# CaRe_Schematic_SMD_6_29.net
KiCad netlist of a schematic drawn in Altium Designer
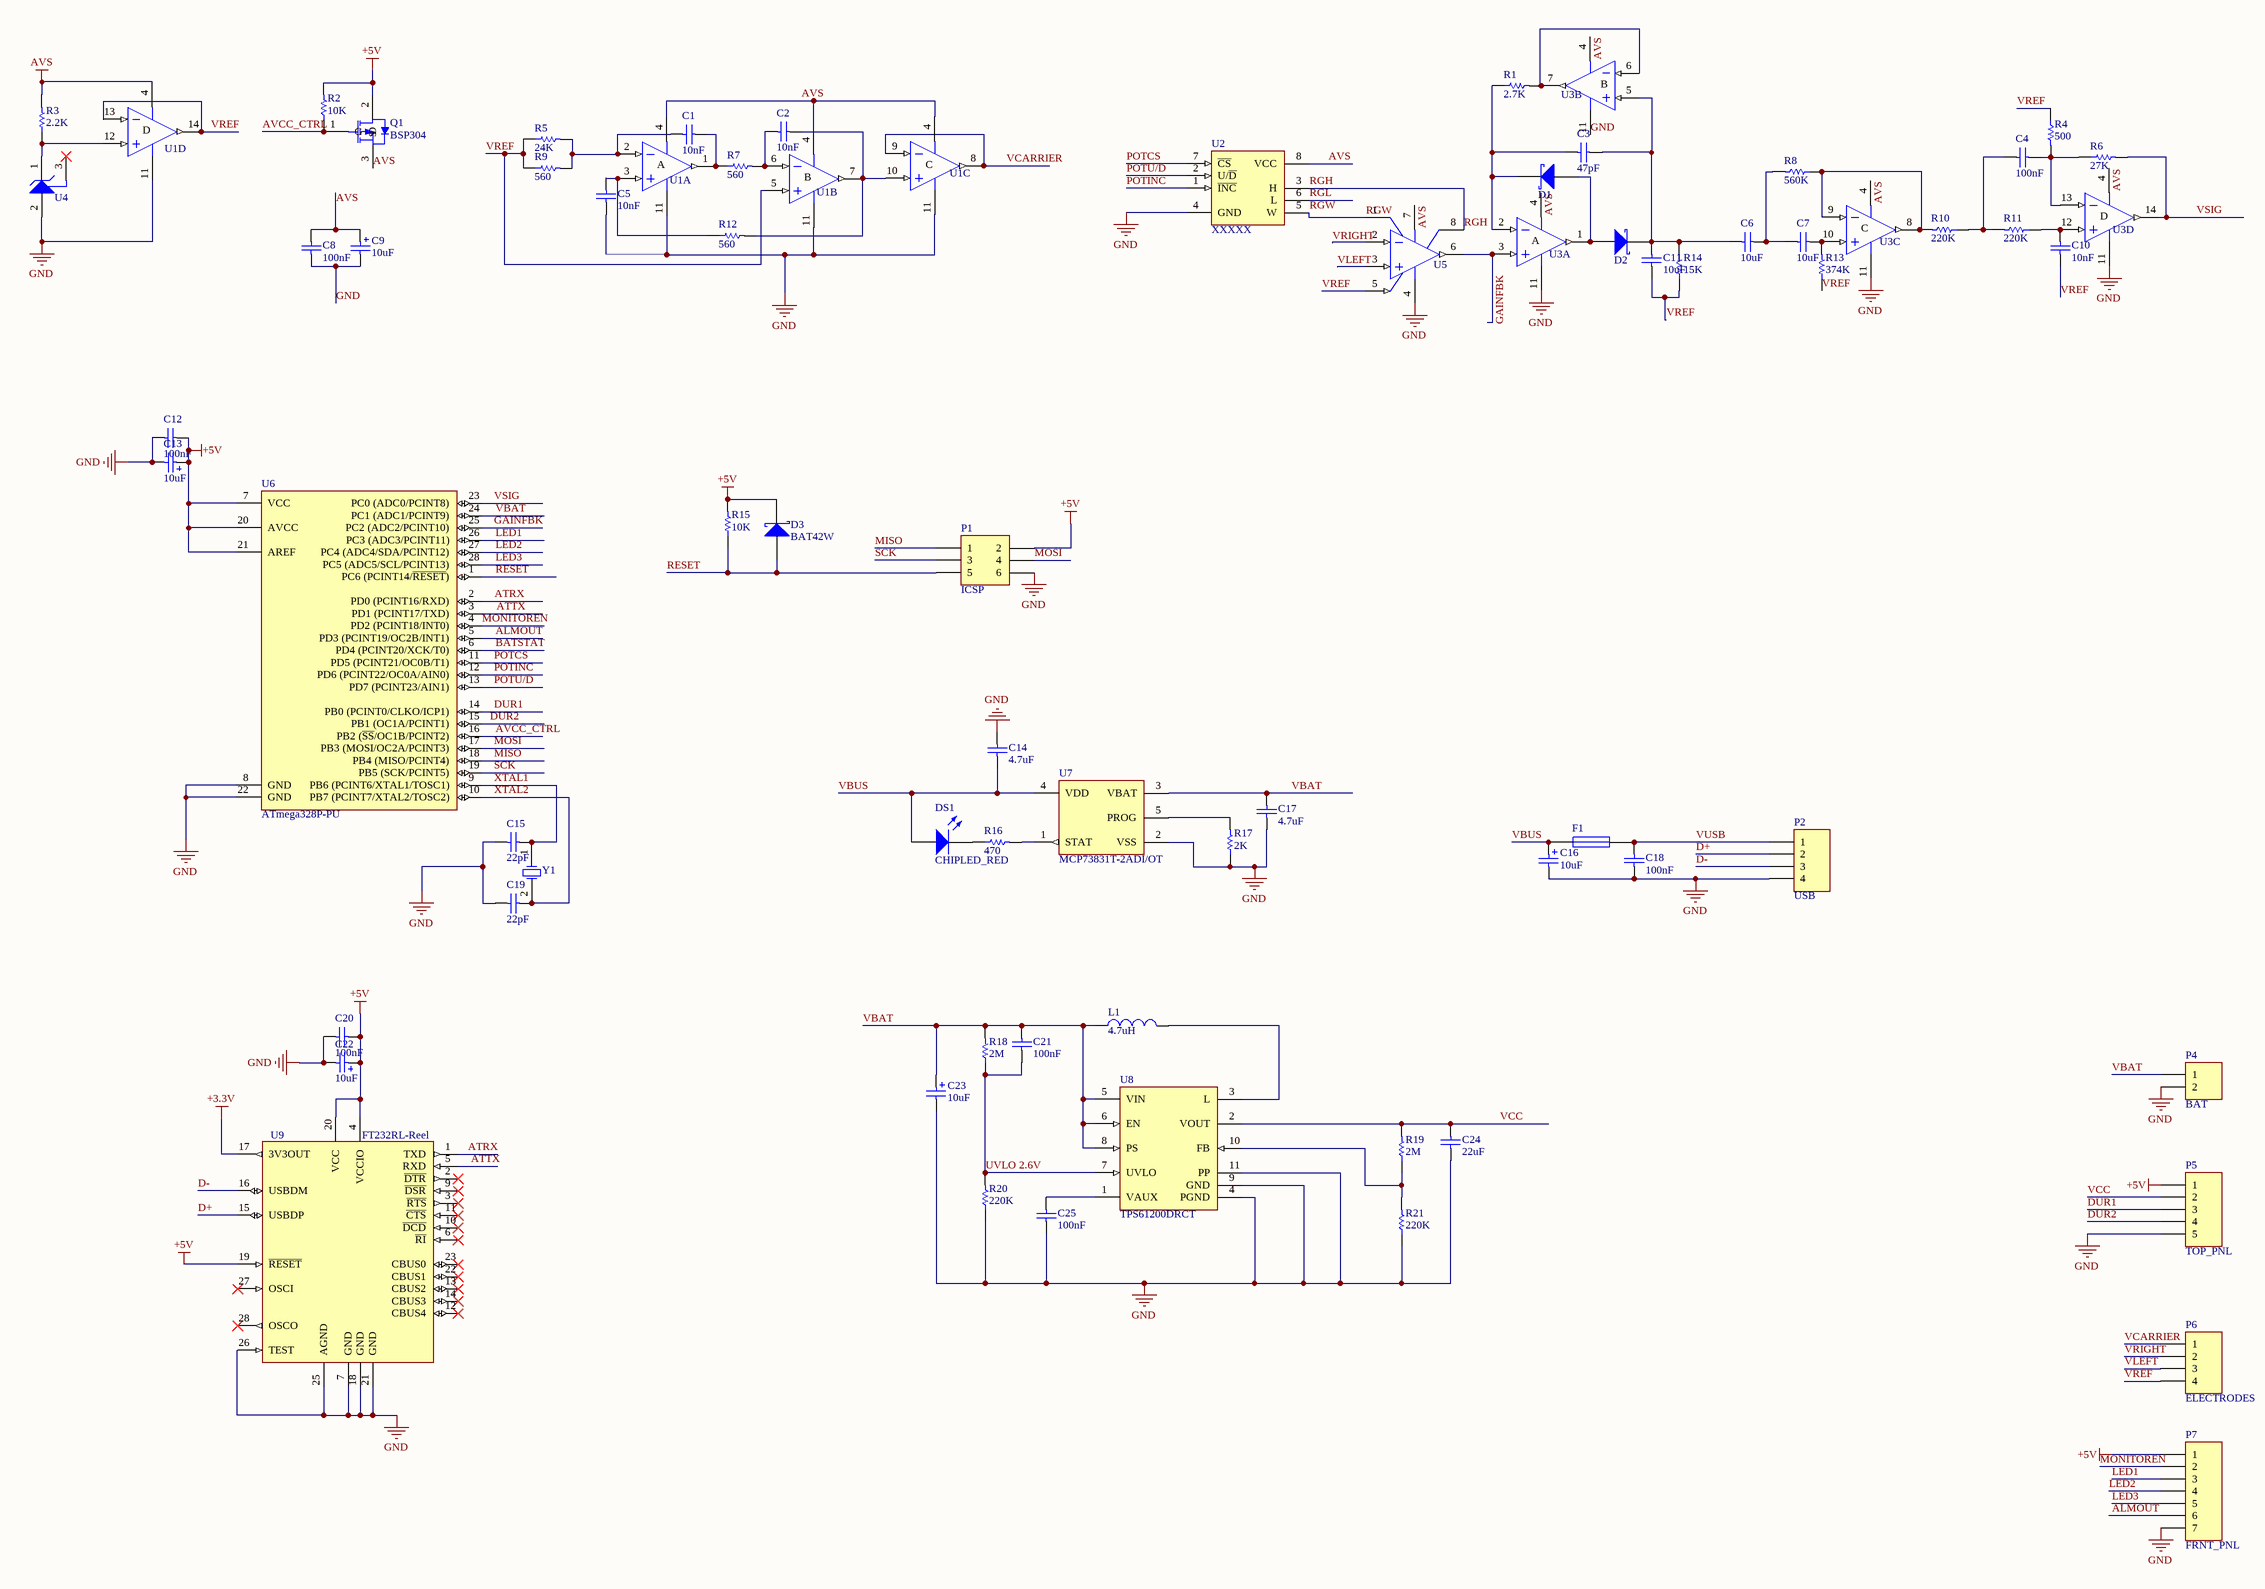
[diagram p0: CaRe_Schematic_SMD_6.29.SchDoc]

(export (version "E")
  (design (tool "Eeschema 10.0.6"))
  (components
    (comp (ref "C1")
      (value "10nF")
      (footprint "CAP0805")
      (description "Capacitor")
      (fields (field (name "PUBLISHER") "Altium Limited"))
      (libsource (lib "CaRe_SchematicLib") (part "Chip Cap"))
    )
    (comp (ref "C2")
      (value "10nF")
      (footprint "CAP0805")
      (description "Capacitor")
      (fields (field (name "PUBLISHER") "Altium Limited"))
      (libsource (lib "CaRe_SchematicLib") (part "Chip Cap"))
    )
    (comp (ref "C3")
      (value "47pF")
      (footprint "CAP0805")
      (description "Capacitor")
      (fields (field (name "PUBLISHER") "Altium Limited"))
      (libsource (lib "CaRe_SchematicLib") (part "Chip Cap"))
    )
    (comp (ref "C4")
      (value "100nF")
      (footprint "CAP0805")
      (description "Capacitor")
      (fields (field (name "PUBLISHER") "Altium Limited"))
      (libsource (lib "CaRe_SchematicLib") (part "Chip Cap"))
    )
    (comp (ref "C5")
      (value "10nF")
      (footprint "CAP0805")
      (description "Capacitor")
      (fields (field (name "PUBLISHER") "Altium Limited"))
      (libsource (lib "CaRe_SchematicLib") (part "Chip Cap"))
    )
    (comp (ref "C6")
      (value "10uF")
      (footprint "CAP0805")
      (description "Capacitor")
      (fields (field (name "PUBLISHER") "Altium Limited"))
      (libsource (lib "CaRe_SchematicLib") (part "Chip Cap"))
    )
    (comp (ref "C7")
      (value "10uF")
      (footprint "CAP0805")
      (description "Capacitor")
      (fields (field (name "PUBLISHER") "Altium Limited"))
      (libsource (lib "CaRe_SchematicLib") (part "Chip Cap"))
    )
    (comp (ref "C8")
      (value "100nF")
      (footprint "CAP0805")
      (description "Capacitor")
      (fields (field (name "PUBLISHER") "Altium Limited"))
      (libsource (lib "CaRe_SchematicLib") (part "Chip Cap"))
    )
    (comp (ref "C9")
      (value "10uF")
      (footprint "0805TANTCAP")
      (description "Polarized Capacitor (Radial)")
      (fields
        (field (name "MANUFACTURER") "AVX")
        (field (name "PART NUMBER") "TAJP106M010RNJ")
        (field (name "PUBLISHER") "Altium Limited")
      )
      (libsource (lib "CaRe_SchematicLib") (part "Cap Tant"))
    )
    (comp (ref "C10")
      (value "10nF")
      (footprint "CAP0805")
      (description "Capacitor")
      (fields (field (name "PUBLISHER") "Altium Limited"))
      (libsource (lib "CaRe_SchematicLib") (part "Chip Cap"))
    )
    (comp (ref "C11")
      (value "10uF")
      (footprint "CAP0805")
      (description "Capacitor")
      (fields (field (name "PUBLISHER") "Altium Limited"))
      (libsource (lib "CaRe_SchematicLib") (part "Chip Cap"))
    )
    (comp (ref "C12")
      (value "100nF")
      (footprint "CAP0805")
      (description "Capacitor")
      (fields (field (name "PUBLISHER") "Altium Limited"))
      (libsource (lib "CaRe_SchematicLib") (part "Chip Cap"))
    )
    (comp (ref "C13")
      (value "10uF")
      (footprint "0805TANTCAP")
      (description "Polarized Capacitor (Radial)")
      (fields
        (field (name "MANUFACTURER") "AVX")
        (field (name "PART NUMBER") "TAJP106M010RNJ")
        (field (name "PUBLISHER") "Altium Limited")
      )
      (libsource (lib "CaRe_SchematicLib") (part "Cap Tant"))
    )
    (comp (ref "C14")
      (value "4.7uF")
      (footprint "CAP0805")
      (description "Capacitor")
      (fields (field (name "PUBLISHER") "Altium Limited"))
      (libsource (lib "CaRe_SchematicLib") (part "Chip Cap"))
    )
    (comp (ref "C15")
      (value "22pF")
      (footprint "CAP0805")
      (description "Capacitor")
      (fields (field (name "PUBLISHER") "Altium Limited"))
      (libsource (lib "CaRe_SchematicLib") (part "Chip Cap"))
    )
    (comp (ref "C16")
      (value "10uF")
      (footprint "0805TANTCAP")
      (description "Polarized Capacitor (Radial)")
      (fields
        (field (name "MANUFACTURER") "AVX")
        (field (name "PART NUMBER") "TAJP106M010RNJ")
        (field (name "PUBLISHER") "Altium Limited")
      )
      (libsource (lib "CaRe_SchematicLib") (part "Cap Tant"))
    )
    (comp (ref "C17")
      (value "4.7uF")
      (footprint "CAP0805")
      (description "Capacitor")
      (fields (field (name "PUBLISHER") "Altium Limited"))
      (libsource (lib "CaRe_SchematicLib") (part "Chip Cap"))
    )
    (comp (ref "C18")
      (value "100nF")
      (footprint "CAP0805")
      (description "Capacitor")
      (fields (field (name "PUBLISHER") "Altium Limited"))
      (libsource (lib "CaRe_SchematicLib") (part "Chip Cap"))
    )
    (comp (ref "C19")
      (value "22pF")
      (footprint "CAP0805")
      (description "Capacitor")
      (fields (field (name "PUBLISHER") "Altium Limited"))
      (libsource (lib "CaRe_SchematicLib") (part "Chip Cap"))
    )
    (comp (ref "C20")
      (value "100nF")
      (footprint "CAP0805")
      (description "Capacitor")
      (fields (field (name "PUBLISHER") "Altium Limited"))
      (libsource (lib "CaRe_SchematicLib") (part "Chip Cap"))
    )
    (comp (ref "C21")
      (value "100nF")
      (footprint "CAP0805")
      (description "Capacitor")
      (fields (field (name "PUBLISHER") "Altium Limited"))
      (libsource (lib "CaRe_SchematicLib") (part "Chip Cap"))
    )
    (comp (ref "C22")
      (value "10uF")
      (footprint "0805TANTCAP")
      (description "Polarized Capacitor (Radial)")
      (fields
        (field (name "MANUFACTURER") "AVX")
        (field (name "PART NUMBER") "TAJP106M010RNJ")
        (field (name "PUBLISHER") "Altium Limited")
      )
      (libsource (lib "CaRe_SchematicLib") (part "Cap Tant"))
    )
    (comp (ref "C23")
      (value "10uF")
      (footprint "0805TANTCAP")
      (description "Polarized Capacitor (Radial)")
      (fields
        (field (name "MANUFACTURER") "AVX")
        (field (name "PART NUMBER") "TAJP106M010RNJ")
        (field (name "PUBLISHER") "Altium Limited")
      )
      (libsource (lib "CaRe_SchematicLib") (part "Cap Tant"))
    )
    (comp (ref "C24")
      (value "22uF")
      (footprint "CAP0805")
      (description "Capacitor")
      (fields (field (name "PUBLISHER") "Altium Limited"))
      (libsource (lib "CaRe_SchematicLib") (part "Chip Cap"))
    )
    (comp (ref "C25")
      (value "100nF")
      (footprint "CAP0805")
      (description "Capacitor")
      (fields (field (name "PUBLISHER") "Altium Limited"))
      (libsource (lib "CaRe_SchematicLib") (part "Chip Cap"))
    )
    (comp (ref "D1")
      (value "BAT42W")
      (footprint "SOD-523")
      (description "Schottky Diode")
      (fields (field (name "MANUFACTURER") "Vishay") (field (name "PUBLISHER") "Altium Limited"))
      (libsource (lib "CaRe_SchematicLib") (part "BAT42W"))
    )
    (comp (ref "D2")
      (value "BAT42W")
      (footprint "SOD-523")
      (description "Schottky Diode")
      (fields (field (name "MANUFACTURER") "Vishay") (field (name "PUBLISHER") "Altium Limited"))
      (libsource (lib "CaRe_SchematicLib") (part "BAT42W"))
    )
    (comp (ref "D3")
      (value "BAT42W")
      (footprint "SOD-523")
      (description "Schottky Diode")
      (fields (field (name "MANUFACTURER") "Vishay") (field (name "PUBLISHER") "Altium Limited"))
      (libsource (lib "CaRe_SchematicLib") (part "BAT42W"))
    )
    (comp (ref "DS1")
      (value "CHIPLED_RED")
      (footprint "CHIP_LED0805")
      (description "Typical RED LED")
      (fields (field (name "PART NUMBER") "P_100_LTST-C170KRKT") (field (name "PUBLISHER") "Altium Limited"))
      (libsource (lib "CaRe_SchematicLib") (part "CHIPLED_RED"))
    )
    (comp (ref "F1")
      (value "MF-MSMF050-1")
      (footprint "MF-MSMF050 FOOTPRINT")
      (description "PTC Resettable Fuse 500 mA")
      (fields (field (name "PUBLISHER") "Altium Limited"))
      (libsource (lib "CaRe_SchematicLib") (part "PTC Fuse"))
    )
    (comp (ref "L1")
      (value "4.7uH")
      (footprint "INDP4330X10N")
      (description "Inductor")
      (fields (field (name "PUBLISHER") "Altium Limited"))
      (libsource (lib "CaReSchlib1") (part "Inductor"))
    )
    (comp (ref "P1")
      (value "ICSP")
      (footprint "HDR2X3")
      (description "Header, 3-Pin, Dual row")
      (fields (field (name "PUBLISHER") "Altium Limited"))
      (libsource (lib "Miscellaneous Connectors") (part "Header 3X2"))
    )
    (comp (ref "P2")
      (value "USB")
      (footprint "JST 4-Pin SMD")
      (description "Header, 4-Pin")
      (fields (field (name "PUBLISHER") "Altium Limited"))
      (libsource (lib "Miscellaneous Connectors") (part "Header 4"))
    )
    (comp (ref "P4")
      (value "BAT")
      (footprint "JST-2 Pin SMD Connector")
      (description "Header, 2-Pin")
      (fields (field (name "PUBLISHER") "Altium Limited"))
      (libsource (lib "Miscellaneous Connectors") (part "Header 2"))
    )
    (comp (ref "P5")
      (value "TOP_PNL")
      (footprint "JST 5 Pin SMD")
      (description "Header, 5-Pin")
      (fields (field (name "PUBLISHER") "Altium Limited"))
      (libsource (lib "CaRe_SchematicLib") (part "Header 5"))
    )
    (comp (ref "P6")
      (value "ELECTRODES")
      (footprint "JST 4-Pin SMD")
      (description "Header, 4-Pin")
      (fields (field (name "PUBLISHER") "Altium Limited"))
      (libsource (lib "Miscellaneous Connectors") (part "Header 4"))
    )
    (comp (ref "P7")
      (value "FRNT_PNL")
      (footprint "JST-SH 7-Pin Vertical SMD")
      (description "Header, 7-Pin")
      (fields (field (name "PUBLISHER") "Altium Limited"))
      (libsource (lib "CaRe_SchematicLib") (part "Header 7"))
    )
    (comp (ref "Q1")
      (value "BSP304")
      (footprint "SOT23_L")
      (description "P-channel Enhancement Mode Vertical D-MOSFET")
      (fields (field (name "PUBLISHER") "Altium Limited"))
      (libsource (lib "Philips Discrete MOSFET - Power") (part "BSP304"))
    )
    (comp (ref "R1")
      (value "2.7K")
      (footprint "RES0805")
      (description "Resistor")
      (fields (field (name "PUBLISHER") "Altium Limited"))
      (libsource (lib "CaRe_SchematicLib") (part "Chip Res"))
    )
    (comp (ref "R2")
      (value "10K")
      (footprint "RES0805")
      (description "Resistor")
      (fields (field (name "PUBLISHER") "Altium Limited"))
      (libsource (lib "CaRe_SchematicLib") (part "Chip Res"))
    )
    (comp (ref "R3")
      (value "2.2K")
      (footprint "RES0805")
      (description "Resistor")
      (fields (field (name "PUBLISHER") "Altium Limited"))
      (libsource (lib "CaRe_SchematicLib") (part "Chip Res"))
    )
    (comp (ref "R4")
      (value "500")
      (footprint "RES0805")
      (description "Resistor")
      (fields (field (name "PUBLISHER") "Altium Limited"))
      (libsource (lib "CaRe_SchematicLib") (part "Chip Res"))
    )
    (comp (ref "R5")
      (value "24K")
      (footprint "RES0805")
      (description "Resistor")
      (fields (field (name "PUBLISHER") "Altium Limited"))
      (libsource (lib "CaRe_SchematicLib") (part "Chip Res"))
    )
    (comp (ref "R6")
      (value "27K")
      (footprint "RES0805")
      (description "Resistor")
      (fields (field (name "PUBLISHER") "Altium Limited"))
      (libsource (lib "CaRe_SchematicLib") (part "Chip Res"))
    )
    (comp (ref "R7")
      (value "560")
      (footprint "RES0805")
      (description "Resistor")
      (fields (field (name "PUBLISHER") "Altium Limited"))
      (libsource (lib "CaRe_SchematicLib") (part "Chip Res"))
    )
    (comp (ref "R8")
      (value "560K")
      (footprint "RES0805")
      (description "Resistor")
      (fields (field (name "PUBLISHER") "Altium Limited"))
      (libsource (lib "CaRe_SchematicLib") (part "Chip Res"))
    )
    (comp (ref "R9")
      (value "560")
      (footprint "RES0805")
      (description "Resistor")
      (fields (field (name "PUBLISHER") "Altium Limited"))
      (libsource (lib "CaRe_SchematicLib") (part "Chip Res"))
    )
    (comp (ref "R10")
      (value "220K")
      (footprint "RES0805")
      (description "Resistor")
      (fields (field (name "PUBLISHER") "Altium Limited"))
      (libsource (lib "CaRe_SchematicLib") (part "Chip Res"))
    )
    (comp (ref "R11")
      (value "220K")
      (footprint "RES0805")
      (description "Resistor")
      (fields (field (name "PUBLISHER") "Altium Limited"))
      (libsource (lib "CaRe_SchematicLib") (part "Chip Res"))
    )
    (comp (ref "R12")
      (value "560")
      (footprint "RES0805")
      (description "Resistor")
      (fields (field (name "PUBLISHER") "Altium Limited"))
      (libsource (lib "CaRe_SchematicLib") (part "Chip Res"))
    )
    (comp (ref "R13")
      (value "374K")
      (footprint "RES0805")
      (description "Resistor")
      (fields (field (name "PUBLISHER") "Altium Limited"))
      (libsource (lib "CaRe_SchematicLib") (part "Chip Res"))
    )
    (comp (ref "R14")
      (value "15K")
      (footprint "RES0805")
      (description "Resistor")
      (fields (field (name "PUBLISHER") "Altium Limited"))
      (libsource (lib "CaRe_SchematicLib") (part "Chip Res"))
    )
    (comp (ref "R15")
      (value "10K")
      (footprint "RES0805")
      (description "Resistor")
      (fields (field (name "PUBLISHER") "Altium Limited"))
      (libsource (lib "CaRe_SchematicLib") (part "Chip Res"))
    )
    (comp (ref "R16")
      (value "470")
      (footprint "RES0805")
      (description "Resistor")
      (fields (field (name "PUBLISHER") "Altium Limited"))
      (libsource (lib "CaRe_SchematicLib") (part "Chip Res"))
    )
    (comp (ref "R17")
      (value "2K")
      (footprint "RES0805")
      (description "Resistor")
      (fields (field (name "PUBLISHER") "Altium Limited"))
      (libsource (lib "CaRe_SchematicLib") (part "Chip Res"))
    )
    (comp (ref "R18")
      (value "2M")
      (footprint "RES0805")
      (description "Resistor")
      (fields (field (name "PUBLISHER") "Altium Limited"))
      (libsource (lib "CaRe_SchematicLib") (part "Chip Res"))
    )
    (comp (ref "R19")
      (value "2M")
      (footprint "RES0805")
      (description "Resistor")
      (fields (field (name "PUBLISHER") "Altium Limited"))
      (libsource (lib "CaRe_SchematicLib") (part "Chip Res"))
    )
    (comp (ref "R20")
      (value "220K")
      (footprint "RES0805")
      (description "Resistor")
      (fields (field (name "PUBLISHER") "Altium Limited"))
      (libsource (lib "CaRe_SchematicLib") (part "Chip Res"))
    )
    (comp (ref "R21")
      (value "220K")
      (footprint "RES0805")
      (description "Resistor")
      (fields (field (name "PUBLISHER") "Altium Limited"))
      (libsource (lib "CaRe_SchematicLib") (part "Chip Res"))
    )
    (comp (ref "U1")
      (value "TLV274IN")
      (footprint "TI-D14_L")
      (description "JFET-Input Operational Amplifier")
      (fields (field (name "PUBLISHER") "Altium Limited"))
      (libsource (lib "CaReSchlib1") (part "TLV274IN"))
    )
    (comp (ref "U2")
      (value "XXXXX")
      (footprint "SOIC-8")
      (description "Nonvolatile Trimmer Potentiometer")
      (fields (field (name "PUBLISHER") "Altium Limited"))
      (libsource (lib "Dallas Interface Digital Potentiometer") (part "DS1804-050"))
    )
    (comp (ref "U3")
      (value "TLV274IN")
      (footprint "TI-D14_L")
      (description "JFET-Input Operational Amplifier")
      (fields (field (name "PUBLISHER") "Altium Limited"))
      (libsource (lib "CaReSchlib1") (part "TLV274IN"))
    )
    (comp (ref "U4")
      (value "LM4040")
      (footprint "SOT23_L")
      (fields (field (name "PARTNUMBER") "LM4040A25IDBZR") (field (name "MANUFACTURER") "Texas Instruments"))
      (libsource (lib "CaRe_SchematicLib") (part "LM4040"))
    )
    (comp (ref "U5")
      (value "LT1920")
      (footprint "LT-S8-8_L(LT1920)")
      (description "Low-Cost, Low-Power Instrumentation Amplifier")
      (fields (field (name "PUBLISHER") "Altium Limited"))
      (libsource (lib "AD Instrumentation Amplifier") (part "AD620AN"))
    )
    (comp (ref "U6")
      (value "ATmega328P-PU")
      (footprint "28P3")
      (fields (field (name "PUBLISHER") "Altium Limited"))
      (libsource (lib "CaReSchlib1") (part "ATmega328P-PU"))
    )
    (comp (ref "U7")
      (value "MCP73831T-2ADI/OT")
      (footprint "SOT-23-OT5_L")
      (fields (field (name "MANUFACTURER") "Microchip"))
      (libsource (lib "CaRe_SchematicLib") (part "MCP73831T-2ADI/OT"))
    )
    (comp (ref "U8")
      (value "TPS61200DRCT")
      (footprint "DRC10-2400X1650TP")
      (fields (field (name "MANUFACTURER") "Texas Instruments"))
      (libsource (lib "CaRe_SchematicLib") (part "TPS61200DRCT"))
    )
    (comp (ref "U9")
      (value "FT232RL-Reel")
      (footprint "SSOP-28_L(FTDI)")
      (description "USB UART Asynchronous Serial Data Transfer Chip, SSOP-28, Tape and Reel")
      (fields (field (name "PUBLISHER") "Altium Limited"))
      (libsource (lib "FTDI Communication UART") (part "FT232RL-Reel"))
    )
    (comp (ref "Y1")
      (value "ECS-10-3-1")
      (footprint "HC-49U")
      (description "Crystal Oscillator")
      (fields (field (name "PUBLISHER") "Altium Limited"))
      (libsource (lib "ECS Crystal Oscillator") (part "ECS-10-13-1"))
    )
  )
  (nets
    (net (code "1") (name "+3.3V") (class "Default")
      (node (ref "U9") (pin "17") (pinfunction "3V3OUT_17") (pintype "output"))
    )
    (net (code "2") (name "+5V") (class "Default")
      (node (ref "C12") (pin "1") (pinfunction "1_1") (pintype "passive"))
      (node (ref "C13") (pin "1") (pinfunction "1_1") (pintype "passive"))
      (node (ref "C20") (pin "1") (pinfunction "1_1") (pintype "passive"))
      (node (ref "C22") (pin "1") (pinfunction "1_1") (pintype "passive"))
      (node (ref "D3") (pin "2") (pinfunction "2_2") (pintype "passive"))
      (node (ref "P1") (pin "2") (pinfunction "2_2") (pintype "passive"))
      (node (ref "P5") (pin "1") (pinfunction "1_1") (pintype "passive"))
      (node (ref "P7") (pin "1") (pinfunction "1_1") (pintype "passive"))
      (node (ref "Q1") (pin "2") (pinfunction "D_2") (pintype "passive"))
      (node (ref "R15") (pin "2") (pinfunction "2_2") (pintype "passive"))
      (node (ref "R2") (pin "2") (pinfunction "2_2") (pintype "passive"))
      (node (ref "U6") (pin "20") (pinfunction "AVCC_20") (pintype "power_in"))
      (node (ref "U6") (pin "21") (pinfunction "AREF_21") (pintype "power_in"))
      (node (ref "U6") (pin "7") (pinfunction "VCC_7") (pintype "power_in"))
      (node (ref "U9") (pin "19") (pinfunction "~{RESET}_19") (pintype "input"))
      (node (ref "U9") (pin "20") (pinfunction "VCC_20") (pintype "power_in"))
      (node (ref "U9") (pin "4") (pinfunction "VCCIO_4") (pintype "power_in"))
    )
    (net (code "3") (name "/ALMOUT") (class "Default")
      (node (ref "P7") (pin "6") (pinfunction "6_6") (pintype "passive"))
      (node (ref "U6") (pin "5") (pinfunction "PD3_(PCINT19/OC2B/INT1)_5") (pintype "bidirectional"))
    )
    (net (code "4") (name "/ATRX") (class "Default")
      (node (ref "U6") (pin "2") (pinfunction "PD0_(PCINT16/RXD)_2") (pintype "bidirectional"))
      (node (ref "U9") (pin "1") (pinfunction "TXD_1") (pintype "output"))
    )
    (net (code "5") (name "/ATTX") (class "Default")
      (node (ref "U6") (pin "3") (pinfunction "PD1_(PCINT17/TXD)_3") (pintype "bidirectional"))
      (node (ref "U9") (pin "5") (pinfunction "RXD_5") (pintype "input"))
    )
    (net (code "6") (name "/AVCC_CTRL") (class "Default")
      (node (ref "Q1") (pin "1") (pinfunction "G_1") (pintype "passive"))
      (node (ref "R2") (pin "1") (pinfunction "1_1") (pintype "passive"))
      (node (ref "U6") (pin "16") (pinfunction "PB2_(~{SS}/OC1B/PCINT2)_16") (pintype "bidirectional"))
    )
    (net (code "7") (name "/BATSTAT") (class "Default")
      (node (ref "U6") (pin "6") (pinfunction "PD4_(PCINT20/XCK/T0)_6") (pintype "bidirectional"))
    )
    (net (code "8") (name "/D+") (class "Default")
      (node (ref "P2") (pin "2") (pinfunction "2_2") (pintype "passive"))
      (node (ref "U9") (pin "15") (pinfunction "USBDP_15") (pintype "bidirectional"))
    )
    (net (code "9") (name "/D-") (class "Default")
      (node (ref "P2") (pin "3") (pinfunction "3_3") (pintype "passive"))
      (node (ref "U9") (pin "16") (pinfunction "USBDM_16") (pintype "bidirectional"))
    )
    (net (code "10") (name "/DUR1") (class "Default")
      (node (ref "P5") (pin "3") (pinfunction "3_3") (pintype "passive"))
      (node (ref "U6") (pin "14") (pinfunction "PB0_(PCINT0/CLKO/ICP1)_14") (pintype "bidirectional"))
    )
    (net (code "11") (name "/DUR2") (class "Default")
      (node (ref "P5") (pin "4") (pinfunction "4_4") (pintype "passive"))
      (node (ref "U6") (pin "15") (pinfunction "PB1_(OC1A/PCINT1)_15") (pintype "bidirectional"))
    )
    (net (code "12") (name "/GAINFBK") (class "Default")
      (node (ref "U3") (pin "3") (pinfunction "IN+_3") (pintype "input"))
      (node (ref "U5") (pin "6") (pinfunction "OUT_6") (pintype "output"))
      (node (ref "U6") (pin "25") (pinfunction "PC2_(ADC2/PCINT10)_25") (pintype "bidirectional"))
    )
    (net (code "13") (name "/LED1") (class "Default")
      (node (ref "P7") (pin "3") (pinfunction "3_3") (pintype "passive"))
      (node (ref "U6") (pin "26") (pinfunction "PC3_(ADC3/PCINT11)_26") (pintype "bidirectional"))
    )
    (net (code "14") (name "/LED2") (class "Default")
      (node (ref "P7") (pin "4") (pinfunction "4_4") (pintype "passive"))
      (node (ref "U6") (pin "27") (pinfunction "PC4_(ADC4/SDA/PCINT12)_27") (pintype "bidirectional"))
    )
    (net (code "15") (name "/LED3") (class "Default")
      (node (ref "P7") (pin "5") (pinfunction "5_5") (pintype "passive"))
      (node (ref "U6") (pin "28") (pinfunction "PC5_(ADC5/SCL/PCINT13)_28") (pintype "bidirectional"))
    )
    (net (code "16") (name "/MISO") (class "Default")
      (node (ref "P1") (pin "1") (pinfunction "1_1") (pintype "passive"))
      (node (ref "U6") (pin "18") (pinfunction "PB4_(MISO/PCINT4)_18") (pintype "bidirectional"))
    )
    (net (code "17") (name "/MONITOREN") (class "Default")
      (node (ref "P7") (pin "2") (pinfunction "2_2") (pintype "passive"))
      (node (ref "U6") (pin "4") (pinfunction "PD2_(PCINT18/INT0)_4") (pintype "bidirectional"))
    )
    (net (code "18") (name "/MOSI") (class "Default")
      (node (ref "P1") (pin "4") (pinfunction "4_4") (pintype "passive"))
      (node (ref "U6") (pin "17") (pinfunction "PB3_(MOSI/OC2A/PCINT3)_17") (pintype "bidirectional"))
    )
    (net (code "19") (name "/POTCS") (class "Default")
      (node (ref "U2") (pin "7") (pinfunction "~{CS}_7") (pintype "input"))
      (node (ref "U6") (pin "11") (pinfunction "PD5_(PCINT21/OC0B/T1)_11") (pintype "bidirectional"))
    )
    (net (code "20") (name "/POTINC") (class "Default")
      (node (ref "U2") (pin "1") (pinfunction "~{INC}_1") (pintype "input"))
      (node (ref "U6") (pin "12") (pinfunction "PD6_(PCINT22/OC0A/AIN0)_12") (pintype "bidirectional"))
    )
    (net (code "21") (name "/POTU{slash}D") (class "Default")
      (node (ref "U2") (pin "2") (pinfunction "U/~{D}_2") (pintype "input"))
      (node (ref "U6") (pin "13") (pinfunction "PD7_(PCINT23/AIN1)_13") (pintype "bidirectional"))
    )
    (net (code "22") (name "/RESET") (class "Default")
      (node (ref "D3") (pin "1") (pinfunction "1_1") (pintype "passive"))
      (node (ref "P1") (pin "5") (pinfunction "5_5") (pintype "passive"))
      (node (ref "R15") (pin "1") (pinfunction "1_1") (pintype "passive"))
      (node (ref "U6") (pin "1") (pinfunction "PC6_(PCINT14/~{RESET})_1") (pintype "bidirectional"))
    )
    (net (code "23") (name "/RGH") (class "Default")
      (node (ref "U2") (pin "3") (pinfunction "H_3") (pintype "passive"))
      (node (ref "U5") (pin "8") (pinfunction "RG_8") (pintype "passive"))
    )
    (net (code "24") (name "/RGL") (class "Default")
      (node (ref "U2") (pin "6") (pinfunction "L_6") (pintype "passive"))
    )
    (net (code "25") (name "/RGW") (class "Default")
      (node (ref "U2") (pin "5") (pinfunction "W_5") (pintype "passive"))
      (node (ref "U5") (pin "1") (pinfunction "RG_1") (pintype "passive"))
    )
    (net (code "26") (name "/SCK") (class "Default")
      (node (ref "P1") (pin "3") (pinfunction "3_3") (pintype "passive"))
      (node (ref "U6") (pin "19") (pinfunction "PB5_(SCK/PCINT5)_19") (pintype "bidirectional"))
    )
    (net (code "27") (name "/UVLO 2.6V") (class "Default")
      (node (ref "C21") (pin "1") (pinfunction "1_1") (pintype "passive"))
      (node (ref "R18") (pin "1") (pinfunction "1_1") (pintype "passive"))
      (node (ref "R20") (pin "2") (pinfunction "2_2") (pintype "passive"))
      (node (ref "U8") (pin "7") (pinfunction "UVLO_7") (pintype "input"))
    )
    (net (code "28") (name "/VBAT") (class "Default")
      (node (ref "C17") (pin "2") (pinfunction "2_2") (pintype "passive"))
      (node (ref "C21") (pin "2") (pinfunction "2_2") (pintype "passive"))
      (node (ref "C23") (pin "1") (pinfunction "1_1") (pintype "passive"))
      (node (ref "L1") (pin "1") (pinfunction "1_1") (pintype "passive"))
      (node (ref "P4") (pin "1") (pinfunction "1_1") (pintype "passive"))
      (node (ref "R18") (pin "2") (pinfunction "2_2") (pintype "passive"))
      (node (ref "U6") (pin "24") (pinfunction "PC1_(ADC1/PCINT9)_24") (pintype "bidirectional"))
      (node (ref "U7") (pin "3") (pinfunction "VBAT_3") (pintype "power_in"))
      (node (ref "U8") (pin "5") (pinfunction "VIN_5") (pintype "power_in"))
      (node (ref "U8") (pin "6") (pinfunction "EN_6") (pintype "input"))
      (node (ref "U8") (pin "8") (pinfunction "PS_8") (pintype "input"))
    )
    (net (code "29") (name "/VBUS") (class "Default")
      (node (ref "C14") (pin "2") (pinfunction "2_2") (pintype "passive"))
      (node (ref "C16") (pin "1") (pinfunction "1_1") (pintype "passive"))
      (node (ref "DS1") (pin "1") (pinfunction "A_1") (pintype "passive"))
      (node (ref "F1") (pin "2") (pinfunction "2_2") (pintype "passive"))
      (node (ref "U7") (pin "4") (pinfunction "VDD_4") (pintype "power_in"))
    )
    (net (code "30") (name "/VCARRIER") (class "Default")
      (node (ref "P6") (pin "1") (pinfunction "1_1") (pintype "passive"))
      (node (ref "U1") (pin "8") (pinfunction "OUT_8") (pintype "output"))
      (node (ref "U1") (pin "9") (pinfunction "IN-_9") (pintype "input"))
    )
    (net (code "31") (name "/VCC") (class "Default")
      (node (ref "C24") (pin "1") (pinfunction "1_1") (pintype "passive"))
      (node (ref "P5") (pin "2") (pinfunction "2_2") (pintype "passive"))
      (node (ref "R19") (pin "2") (pinfunction "2_2") (pintype "passive"))
      (node (ref "U8") (pin "2") (pinfunction "VOUT_2") (pintype "power_in"))
    )
    (net (code "32") (name "/VLEFT") (class "Default")
      (node (ref "P6") (pin "3") (pinfunction "3_3") (pintype "passive"))
      (node (ref "U5") (pin "3") (pinfunction "+IN_3") (pintype "input"))
    )
    (net (code "33") (name "/VREF") (class "Default")
      (node (ref "C10") (pin "1") (pinfunction "1_1") (pintype "passive"))
      (node (ref "C11") (pin "1") (pinfunction "1_1") (pintype "passive"))
      (node (ref "P6") (pin "4") (pinfunction "4_4") (pintype "passive"))
      (node (ref "R13") (pin "1") (pinfunction "1_1") (pintype "passive"))
      (node (ref "R14") (pin "1") (pinfunction "1_1") (pintype "passive"))
      (node (ref "R4") (pin "1") (pinfunction "1_1") (pintype "passive"))
      (node (ref "R5") (pin "1") (pinfunction "1_1") (pintype "passive"))
      (node (ref "R9") (pin "1") (pinfunction "1_1") (pintype "passive"))
      (node (ref "U1") (pin "13") (pinfunction "IN-_13") (pintype "input"))
      (node (ref "U1") (pin "14") (pinfunction "OUT_14") (pintype "output"))
      (node (ref "U1") (pin "5") (pinfunction "IN+_5") (pintype "input"))
      (node (ref "U5") (pin "5") (pinfunction "REF_5") (pintype "input"))
    )
    (net (code "34") (name "/VRIGHT") (class "Default")
      (node (ref "P6") (pin "2") (pinfunction "2_2") (pintype "passive"))
      (node (ref "U5") (pin "2") (pinfunction "-IN_2") (pintype "input"))
    )
    (net (code "35") (name "/VSIG") (class "Default")
      (node (ref "R6") (pin "2") (pinfunction "2_2") (pintype "passive"))
      (node (ref "U3") (pin "14") (pinfunction "OUT_14") (pintype "output"))
      (node (ref "U6") (pin "23") (pinfunction "PC0_(ADC0/PCINT8)_23") (pintype "bidirectional"))
    )
    (net (code "36") (name "/VUSB") (class "Default")
      (node (ref "C18") (pin "2") (pinfunction "2_2") (pintype "passive"))
      (node (ref "F1") (pin "1") (pinfunction "1_1") (pintype "passive"))
      (node (ref "P2") (pin "1") (pinfunction "1_1") (pintype "passive"))
    )
    (net (code "37") (name "/XTAL1") (class "Default")
      (node (ref "C15") (pin "2") (pinfunction "2_2") (pintype "passive"))
      (node (ref "U6") (pin "9") (pinfunction "PB6_(PCINT6/XTAL1/TOSC1)_9") (pintype "bidirectional"))
      (node (ref "Y1") (pin "1") (pinfunction "OSC1_1") (pintype "passive"))
    )
    (net (code "38") (name "/XTAL2") (class "Default")
      (node (ref "C19") (pin "2") (pinfunction "2_2") (pintype "passive"))
      (node (ref "U6") (pin "10") (pinfunction "PB7_(PCINT7/XTAL2/TOSC2)_10") (pintype "bidirectional"))
      (node (ref "Y1") (pin "2") (pinfunction "OSC2_2") (pintype "passive"))
    )
    (net (code "39") (name "AVS") (class "Default")
      (node (ref "C8") (pin "2") (pinfunction "2_2") (pintype "passive"))
      (node (ref "C9") (pin "1") (pinfunction "1_1") (pintype "passive"))
      (node (ref "Q1") (pin "3") (pinfunction "S_3") (pintype "passive"))
      (node (ref "R3") (pin "2") (pinfunction "2_2") (pintype "passive"))
      (node (ref "U1") (pin "4") (pinfunction "V+_4") (pintype "power_in"))
      (node (ref "U2") (pin "8") (pinfunction "VCC_8") (pintype "power_in"))
      (node (ref "U3") (pin "4") (pinfunction "V+_4") (pintype "power_in"))
      (node (ref "U5") (pin "7") (pinfunction "V+_7") (pintype "power_in"))
    )
    (net (code "40") (name "GND") (class "Default")
      (node (ref "C12") (pin "2") (pinfunction "2_2") (pintype "passive"))
      (node (ref "C13") (pin "2") (pinfunction "2_2") (pintype "passive"))
      (node (ref "C14") (pin "1") (pinfunction "1_1") (pintype "passive"))
      (node (ref "C15") (pin "1") (pinfunction "1_1") (pintype "passive"))
      (node (ref "C16") (pin "2") (pinfunction "2_2") (pintype "passive"))
      (node (ref "C17") (pin "1") (pinfunction "1_1") (pintype "passive"))
      (node (ref "C18") (pin "1") (pinfunction "1_1") (pintype "passive"))
      (node (ref "C19") (pin "1") (pinfunction "1_1") (pintype "passive"))
      (node (ref "C20") (pin "2") (pinfunction "2_2") (pintype "passive"))
      (node (ref "C22") (pin "2") (pinfunction "2_2") (pintype "passive"))
      (node (ref "C23") (pin "2") (pinfunction "2_2") (pintype "passive"))
      (node (ref "C24") (pin "2") (pinfunction "2_2") (pintype "passive"))
      (node (ref "C25") (pin "1") (pinfunction "1_1") (pintype "passive"))
      (node (ref "C5") (pin "1") (pinfunction "1_1") (pintype "passive"))
      (node (ref "C8") (pin "1") (pinfunction "1_1") (pintype "passive"))
      (node (ref "C9") (pin "2") (pinfunction "2_2") (pintype "passive"))
      (node (ref "P1") (pin "6") (pinfunction "6_6") (pintype "passive"))
      (node (ref "P2") (pin "4") (pinfunction "4_4") (pintype "passive"))
      (node (ref "P4") (pin "2") (pinfunction "2_2") (pintype "passive"))
      (node (ref "P5") (pin "5") (pinfunction "5_5") (pintype "passive"))
      (node (ref "P7") (pin "7") (pinfunction "7_7") (pintype "passive"))
      (node (ref "R17") (pin "1") (pinfunction "1_1") (pintype "passive"))
      (node (ref "R20") (pin "1") (pinfunction "1_1") (pintype "passive"))
      (node (ref "R21") (pin "1") (pinfunction "1_1") (pintype "passive"))
      (node (ref "U1") (pin "11") (pinfunction "V-_11") (pintype "power_in"))
      (node (ref "U2") (pin "4") (pinfunction "GND_4") (pintype "power_in"))
      (node (ref "U3") (pin "11") (pinfunction "V-_11") (pintype "power_in"))
      (node (ref "U4") (pin "2") (pinfunction "ANODE_2") (pintype "passive"))
      (node (ref "U5") (pin "4") (pinfunction "V-_4") (pintype "power_in"))
      (node (ref "U6") (pin "22") (pinfunction "GND_22") (pintype "power_in"))
      (node (ref "U6") (pin "8") (pinfunction "GND_8") (pintype "power_in"))
      (node (ref "U7") (pin "2") (pinfunction "VSS_2") (pintype "power_in"))
      (node (ref "U8") (pin "11") (pinfunction "PP_11") (pintype "power_in"))
      (node (ref "U8") (pin "4") (pinfunction "PGND_4") (pintype "power_in"))
      (node (ref "U8") (pin "9") (pinfunction "GND_9") (pintype "power_in"))
      (node (ref "U9") (pin "18") (pinfunction "GND_18") (pintype "power_in"))
      (node (ref "U9") (pin "21") (pinfunction "GND_21") (pintype "power_in"))
      (node (ref "U9") (pin "25") (pinfunction "AGND_25") (pintype "power_in"))
      (node (ref "U9") (pin "26") (pinfunction "TEST_26") (pintype "input"))
      (node (ref "U9") (pin "7") (pinfunction "GND_7") (pintype "power_in"))
    )
    (net (code "41") (name "Net-(C4-Pad1)") (class "Default")
      (node (ref "C4") (pin "1") (pinfunction "1_1") (pintype "passive"))
      (node (ref "R10") (pin "1") (pinfunction "1_1") (pintype "passive"))
      (node (ref "R11") (pin "2") (pinfunction "2_2") (pintype "passive"))
    )
    (net (code "42") (name "Net-(C6-Pad1)") (class "Default")
      (node (ref "C6") (pin "1") (pinfunction "1_1") (pintype "passive"))
      (node (ref "C7") (pin "2") (pinfunction "2_2") (pintype "passive"))
      (node (ref "R8") (pin "2") (pinfunction "2_2") (pintype "passive"))
    )
    (net (code "43") (name "Net-(DS1-K)") (class "Default")
      (node (ref "DS1") (pin "2") (pinfunction "K_2") (pintype "passive"))
      (node (ref "R16") (pin "1") (pinfunction "1_1") (pintype "passive"))
    )
    (net (code "44") (name "Net-(U1A-IN+)") (class "Default")
      (node (ref "C5") (pin "2") (pinfunction "2_2") (pintype "passive"))
      (node (ref "R12") (pin "1") (pinfunction "1_1") (pintype "passive"))
      (node (ref "U1") (pin "3") (pinfunction "IN+_3") (pintype "input"))
    )
    (net (code "45") (name "Net-(U1A-IN-)") (class "Default")
      (node (ref "C1") (pin "1") (pinfunction "1_1") (pintype "passive"))
      (node (ref "R5") (pin "2") (pinfunction "2_2") (pintype "passive"))
      (node (ref "R9") (pin "2") (pinfunction "2_2") (pintype "passive"))
      (node (ref "U1") (pin "2") (pinfunction "IN-_2") (pintype "input"))
    )
    (net (code "46") (name "Net-(U1A-OUT)") (class "Default")
      (node (ref "C1") (pin "2") (pinfunction "2_2") (pintype "passive"))
      (node (ref "R7") (pin "1") (pinfunction "1_1") (pintype "passive"))
      (node (ref "U1") (pin "1") (pinfunction "OUT_1") (pintype "output"))
    )
    (net (code "47") (name "Net-(U1B-IN-)") (class "Default")
      (node (ref "C2") (pin "1") (pinfunction "1_1") (pintype "passive"))
      (node (ref "R7") (pin "2") (pinfunction "2_2") (pintype "passive"))
      (node (ref "U1") (pin "6") (pinfunction "IN-_6") (pintype "input"))
    )
    (net (code "48") (name "Net-(U1B-OUT)") (class "Default")
      (node (ref "C2") (pin "2") (pinfunction "2_2") (pintype "passive"))
      (node (ref "R12") (pin "2") (pinfunction "2_2") (pintype "passive"))
      (node (ref "U1") (pin "10") (pinfunction "IN+_10") (pintype "input"))
      (node (ref "U1") (pin "7") (pinfunction "OUT_7") (pintype "output"))
    )
    (net (code "49") (name "Net-(U1D-IN+)") (class "Default")
      (node (ref "R3") (pin "1") (pinfunction "1_1") (pintype "passive"))
      (node (ref "U1") (pin "12") (pinfunction "IN+_12") (pintype "input"))
      (node (ref "U4") (pin "1") (pinfunction "CATHODE_1") (pintype "passive"))
    )
    (net (code "50") (name "Net-(U3A-IN-)") (class "Default")
      (node (ref "C3") (pin "2") (pinfunction "2_2") (pintype "passive"))
      (node (ref "D1") (pin "2") (pinfunction "2_2") (pintype "passive"))
      (node (ref "R1") (pin "1") (pinfunction "1_1") (pintype "passive"))
      (node (ref "U3") (pin "2") (pinfunction "IN-_2") (pintype "input"))
    )
    (net (code "51") (name "Net-(U3A-OUT)") (class "Default")
      (node (ref "D1") (pin "1") (pinfunction "1_1") (pintype "passive"))
      (node (ref "D2") (pin "1") (pinfunction "1_1") (pintype "passive"))
      (node (ref "U3") (pin "1") (pinfunction "OUT_1") (pintype "output"))
    )
    (net (code "52") (name "Net-(U3B-IN+)") (class "Default")
      (node (ref "C11") (pin "2") (pinfunction "2_2") (pintype "passive"))
      (node (ref "C3") (pin "1") (pinfunction "1_1") (pintype "passive"))
      (node (ref "C6") (pin "2") (pinfunction "2_2") (pintype "passive"))
      (node (ref "D2") (pin "2") (pinfunction "2_2") (pintype "passive"))
      (node (ref "R14") (pin "2") (pinfunction "2_2") (pintype "passive"))
      (node (ref "U3") (pin "5") (pinfunction "IN+_5") (pintype "input"))
    )
    (net (code "53") (name "Net-(U3B-IN-)") (class "Default")
      (node (ref "R1") (pin "2") (pinfunction "2_2") (pintype "passive"))
      (node (ref "U3") (pin "6") (pinfunction "IN-_6") (pintype "input"))
      (node (ref "U3") (pin "7") (pinfunction "OUT_7") (pintype "output"))
    )
    (net (code "54") (name "Net-(U3C-IN+)") (class "Default")
      (node (ref "C7") (pin "1") (pinfunction "1_1") (pintype "passive"))
      (node (ref "R13") (pin "2") (pinfunction "2_2") (pintype "passive"))
      (node (ref "U3") (pin "10") (pinfunction "IN+_10") (pintype "input"))
    )
    (net (code "55") (name "Net-(U3C-IN-)") (class "Default")
      (node (ref "R10") (pin "2") (pinfunction "2_2") (pintype "passive"))
      (node (ref "R8") (pin "1") (pinfunction "1_1") (pintype "passive"))
      (node (ref "U3") (pin "8") (pinfunction "OUT_8") (pintype "output"))
      (node (ref "U3") (pin "9") (pinfunction "IN-_9") (pintype "input"))
    )
    (net (code "56") (name "Net-(U3D-IN+)") (class "Default")
      (node (ref "C10") (pin "2") (pinfunction "2_2") (pintype "passive"))
      (node (ref "R11") (pin "1") (pinfunction "1_1") (pintype "passive"))
      (node (ref "U3") (pin "12") (pinfunction "IN+_12") (pintype "input"))
    )
    (net (code "57") (name "Net-(U3D-IN-)") (class "Default")
      (node (ref "C4") (pin "2") (pinfunction "2_2") (pintype "passive"))
      (node (ref "R4") (pin "2") (pinfunction "2_2") (pintype "passive"))
      (node (ref "R6") (pin "1") (pinfunction "1_1") (pintype "passive"))
      (node (ref "U3") (pin "13") (pinfunction "IN-_13") (pintype "input"))
    )
    (net (code "58") (name "Net-(U7-PROG)") (class "Default")
      (node (ref "R17") (pin "2") (pinfunction "2_2") (pintype "passive"))
      (node (ref "U7") (pin "5") (pinfunction "PROG_5") (pintype "passive"))
    )
    (net (code "59") (name "Net-(U7-STAT)") (class "Default")
      (node (ref "R16") (pin "2") (pinfunction "2_2") (pintype "passive"))
      (node (ref "U7") (pin "1") (pinfunction "STAT_1") (pintype "output"))
    )
    (net (code "60") (name "Net-(U8-FB)") (class "Default")
      (node (ref "R19") (pin "1") (pinfunction "1_1") (pintype "passive"))
      (node (ref "R21") (pin "2") (pinfunction "2_2") (pintype "passive"))
      (node (ref "U8") (pin "10") (pinfunction "FB_10") (pintype "input"))
    )
    (net (code "61") (name "Net-(U8-L)") (class "Default")
      (node (ref "L1") (pin "2") (pinfunction "2_2") (pintype "passive"))
      (node (ref "U8") (pin "3") (pinfunction "L_3") (pintype "power_in"))
    )
    (net (code "62") (name "Net-(U8-VAUX)") (class "Default")
      (node (ref "C25") (pin "2") (pinfunction "2_2") (pintype "passive"))
      (node (ref "U8") (pin "1") (pinfunction "VAUX_1") (pintype "power_in"))
    )
    (net (code "63") (name "unconnected-(U4-NC-Pad3)") (class "Default")
      (node (ref "U4") (pin "3") (pinfunction "NC_3") (pintype "passive+no_connect"))
    )
    (net (code "64") (name "unconnected-(U9-CBUS0-Pad23)") (class "Default")
      (node (ref "U9") (pin "23") (pinfunction "CBUS0_23") (pintype "bidirectional+no_connect"))
    )
    (net (code "65") (name "unconnected-(U9-CBUS1-Pad22)") (class "Default")
      (node (ref "U9") (pin "22") (pinfunction "CBUS1_22") (pintype "bidirectional+no_connect"))
    )
    (net (code "66") (name "unconnected-(U9-CBUS2-Pad13)") (class "Default")
      (node (ref "U9") (pin "13") (pinfunction "CBUS2_13") (pintype "bidirectional+no_connect"))
    )
    (net (code "67") (name "unconnected-(U9-CBUS3-Pad14)") (class "Default")
      (node (ref "U9") (pin "14") (pinfunction "CBUS3_14") (pintype "bidirectional+no_connect"))
    )
    (net (code "68") (name "unconnected-(U9-CBUS4-Pad12)") (class "Default")
      (node (ref "U9") (pin "12") (pinfunction "CBUS4_12") (pintype "bidirectional+no_connect"))
    )
    (net (code "69") (name "unconnected-(U9-NC-Pad8)") (class "Default")
      (node (ref "U9") (pin "8") (pinfunction "NC_8") (pintype "passive"))
    )
    (net (code "70") (name "unconnected-(U9-NC-Pad24)") (class "Default")
      (node (ref "U9") (pin "24") (pinfunction "NC_24") (pintype "passive"))
    )
    (net (code "71") (name "unconnected-(U9-OSCI-Pad27)") (class "Default")
      (node (ref "U9") (pin "27") (pinfunction "OSCI_27") (pintype "input+no_connect"))
    )
    (net (code "72") (name "unconnected-(U9-OSCO-Pad28)") (class "Default")
      (node (ref "U9") (pin "28") (pinfunction "OSCO_28") (pintype "output+no_connect"))
    )
    (net (code "73") (name "unconnected-(U9-~{CTS}-Pad11)") (class "Default")
      (node (ref "U9") (pin "11") (pinfunction "~{CTS}_11") (pintype "input+no_connect"))
    )
    (net (code "74") (name "unconnected-(U9-~{DCD}-Pad10)") (class "Default")
      (node (ref "U9") (pin "10") (pinfunction "~{DCD}_10") (pintype "input+no_connect"))
    )
    (net (code "75") (name "unconnected-(U9-~{DSR}-Pad9)") (class "Default")
      (node (ref "U9") (pin "9") (pinfunction "~{DSR}_9") (pintype "input+no_connect"))
    )
    (net (code "76") (name "unconnected-(U9-~{DTR}-Pad2)") (class "Default")
      (node (ref "U9") (pin "2") (pinfunction "~{DTR}_2") (pintype "output+no_connect"))
    )
    (net (code "77") (name "unconnected-(U9-~{RI}-Pad6)") (class "Default")
      (node (ref "U9") (pin "6") (pinfunction "~{RI}_6") (pintype "input+no_connect"))
    )
    (net (code "78") (name "unconnected-(U9-~{RTS}-Pad3)") (class "Default")
      (node (ref "U9") (pin "3") (pinfunction "~{RTS}_3") (pintype "output+no_connect"))
    )
  )
)
